# 02_Schematic.net
KiCad netlist of a schematic drawn in Altium Designer
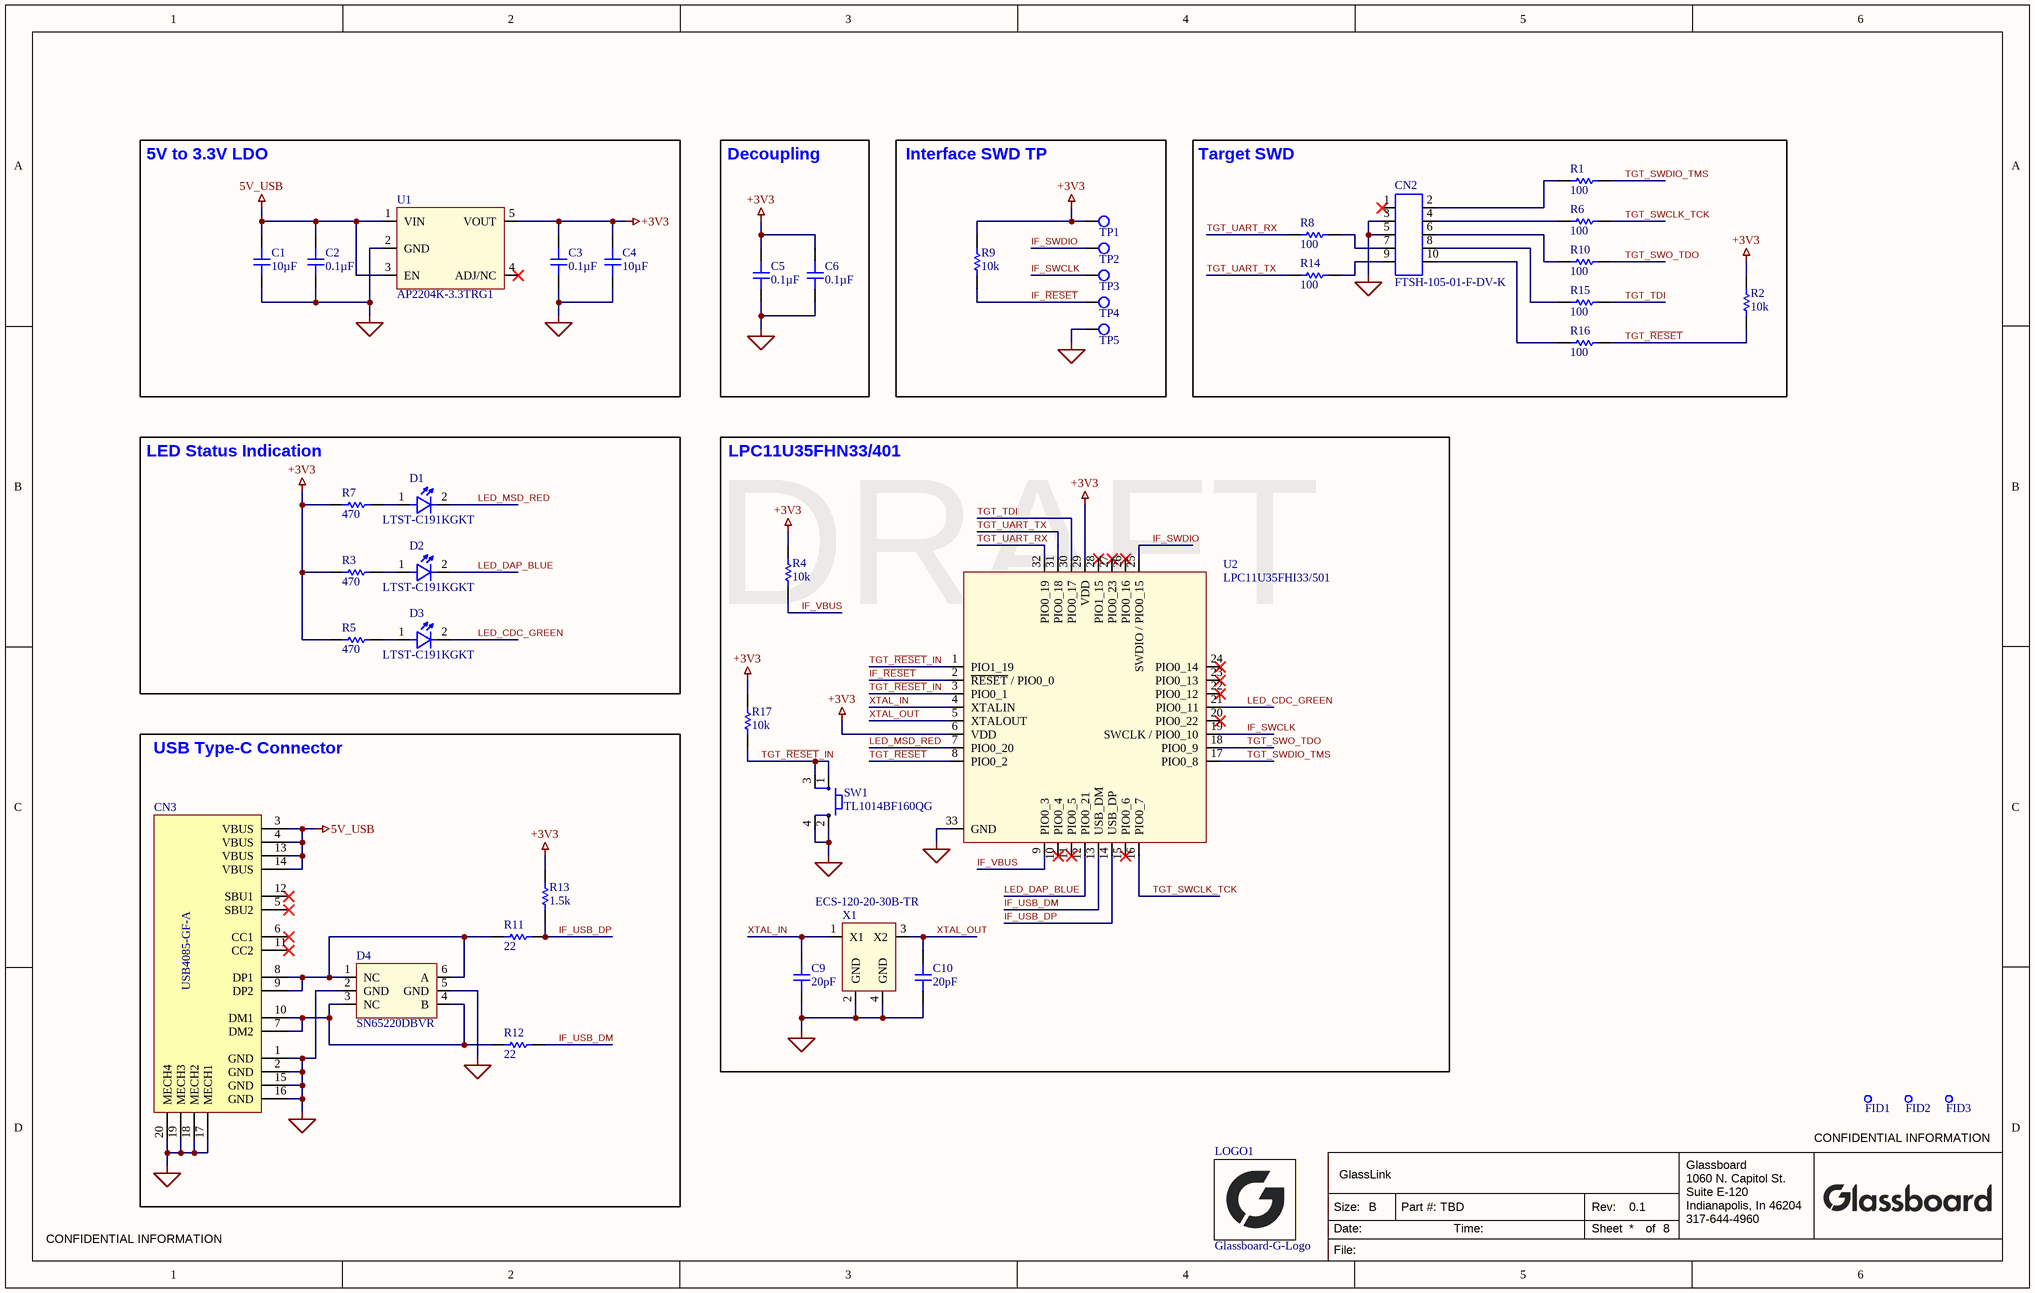
[diagram p0: [02] Schematic.SchDoc]

(export (version "E")
  (design (tool "Eeschema 10.0.6"))
  (components
    (comp (ref "C1")
      (value "10µF")
      (footprint "CAPC0402(1005)70_L")
      (description "CAP CER 10UF 6.3V X5R 0402")
      (fields
        (field (name "PART NUMBER") "CC0402MRX5R5BB106")
        (field (name "TOLERANCE") "0.2")
        (field (name "PUBLISHER") "Randy Parmerlee")
      )
      (libsource (lib "Glassboard Component Database") (part "Capacitor - Non Polarized"))
    )
    (comp (ref "C2")
      (value "0.1µF")
      (footprint "CAPC0402(1005)70_L")
      (description "CAP CER 0.1UF 10V X5R 0402")
      (fields
        (field (name "PART NUMBER") "CGA2B2X5R1A104M050BA")
        (field (name "TOLERANCE") "0.2")
        (field (name "PUBLISHER") "Drew Westrick")
      )
      (libsource (lib "Glassboard Component Database") (part "Capacitor - Non Polarized"))
    )
    (comp (ref "C3")
      (value "0.1µF")
      (footprint "CAPC0402(1005)70_L")
      (description "CAP CER 0.1UF 10V X5R 0402")
      (fields
        (field (name "PART NUMBER") "CGA2B2X5R1A104M050BA")
        (field (name "TOLERANCE") "0.2")
        (field (name "PUBLISHER") "Drew Westrick")
      )
      (libsource (lib "Glassboard Component Database") (part "Capacitor - Non Polarized"))
    )
    (comp (ref "C4")
      (value "10µF")
      (footprint "CAPC0402(1005)70_L")
      (description "CAP CER 10UF 6.3V X5R 0402")
      (fields
        (field (name "PART NUMBER") "CC0402MRX5R5BB106")
        (field (name "TOLERANCE") "0.2")
        (field (name "PUBLISHER") "Randy Parmerlee")
      )
      (libsource (lib "Glassboard Component Database") (part "Capacitor - Non Polarized"))
    )
    (comp (ref "C5")
      (value "0.1µF")
      (footprint "CAPC0402(1005)70_L")
      (description "CAP CER 0.1UF 10V X5R 0402")
      (fields
        (field (name "PART NUMBER") "CGA2B2X5R1A104M050BA")
        (field (name "TOLERANCE") "0.2")
        (field (name "PUBLISHER") "Drew Westrick")
      )
      (libsource (lib "Glassboard Component Database") (part "Capacitor - Non Polarized"))
    )
    (comp (ref "C6")
      (value "0.1µF")
      (footprint "CAPC0402(1005)70_L")
      (description "CAP CER 0.1UF 10V X5R 0402")
      (fields
        (field (name "PART NUMBER") "CGA2B2X5R1A104M050BA")
        (field (name "TOLERANCE") "0.2")
        (field (name "PUBLISHER") "Drew Westrick")
      )
      (libsource (lib "Glassboard Component Database") (part "Capacitor - Non Polarized"))
    )
    (comp (ref "C9")
      (value "20pF")
      (footprint "CAPC0402(1005)70_L")
      (description "CAP CER 20PF 50V C0G/NPO 0402")
      (fields
        (field (name "PART NUMBER") "CC0402JRNPO9BN200")
        (field (name "TOLERANCE") "0.05")
        (field (name "PUBLISHER") "Randy Parmerlee")
      )
      (libsource (lib "Glassboard Component Database") (part "Capacitor - Non Polarized"))
    )
    (comp (ref "C10")
      (value "20pF")
      (footprint "CAPC0402(1005)70_L")
      (description "CAP CER 20PF 50V C0G/NPO 0402")
      (fields
        (field (name "PART NUMBER") "CC0402JRNPO9BN200")
        (field (name "TOLERANCE") "0.05")
        (field (name "PUBLISHER") "Randy Parmerlee")
      )
      (libsource (lib "Glassboard Component Database") (part "Capacitor - Non Polarized"))
    )
    (comp (ref "CN2")
      (value "FTSH-105-01-F-DV-K")
      (footprint "FTSH-105-01-F-DV-K")
      (description "CONN HEADER 10POS DUAL .05\" SMD")
      (fields
        (field (name "MANUFACTURER") "Samtec Inc")
        (field (name "DISTRIBUTOR 1 PART NUMBER") "SAM8796-ND")
        (field (name "PUBLISHER") "Drew Westrick")
      )
      (libsource (lib "Glassboard Component Database") (part "CONN HEADER 10 POS DUAL ROW"))
    )
    (comp (ref "CN3")
      (value "USB4085-GF-A")
      (footprint "USB4085-GF-A")
      (description "CONN RCPT USB2.0 TYPEC 16POS")
      (fields
        (field (name "MANUFACTURER") "GCT")
        (field (name "DISTRIBUTOR 1 PART NUMBER") "2073-USB4085-GF-ACT-ND")
        (field (name "PUBLISHER") "Stephen Murphy")
      )
      (libsource (lib "Glassboard Component Database") (part "USB4085-GF-A"))
    )
    (comp (ref "D1")
      (value "LTST-C191KGKT")
      (footprint "LTST-C191KGKT")
      (description "LED GREEN CLEAR THIN 0603 SMD")
      (fields
        (field (name "MANUFACTURER") "Lite-On Inc")
        (field (name "DISTRIBUTOR 1 PART NUMBER") "160-1446-1-ND")
        (field (name "PUBLISHER") "Randy Parmerlee")
      )
      (libsource (lib "Glassboard Component Database") (part "Standard LED"))
    )
    (comp (ref "D2")
      (value "LTST-C191KGKT")
      (footprint "LTST-C191KGKT")
      (description "LED GREEN CLEAR THIN 0603 SMD")
      (fields
        (field (name "MANUFACTURER") "Lite-On Inc")
        (field (name "DISTRIBUTOR 1 PART NUMBER") "160-1446-1-ND")
        (field (name "PUBLISHER") "Randy Parmerlee")
      )
      (libsource (lib "Glassboard Component Database") (part "Standard LED"))
    )
    (comp (ref "D3")
      (value "LTST-C191KGKT")
      (footprint "LTST-C191KGKT")
      (description "LED GREEN CLEAR THIN 0603 SMD")
      (fields
        (field (name "MANUFACTURER") "Lite-On Inc")
        (field (name "DISTRIBUTOR 1 PART NUMBER") "160-1446-1-ND")
        (field (name "PUBLISHER") "Randy Parmerlee")
      )
      (libsource (lib "Glassboard Component Database") (part "Standard LED"))
    )
    (comp (ref "D4")
      (value "SN65220DBVR")
      (footprint "SN65220DBVR-L")
      (description "IC SINGLE USB PORT TVS SOT-23-6")
      (fields
        (field (name "VOLTAGE") "5V")
        (field (name "MANUFACTURER") "Texas Instruments")
        (field (name "PUBLISHER") "Randy Parmerlee")
      )
      (libsource (lib "Glassboard Component Database") (part "SN65220DBVR"))
    )
    (comp (ref "FID1")
      (value "FID")
      (footprint "fid_30mil")
      (description "Surface Mount Fiducials")
      (fields (field (name "PART NUMBER") "Fiducial") (field (name "PUBLISHER") "Randy Parmerlee"))
      (libsource (lib "Glassboard Component Database") (part "Fiducial"))
    )
    (comp (ref "FID2")
      (value "FID")
      (footprint "fid_30mil")
      (description "Surface Mount Fiducials")
      (fields (field (name "PART NUMBER") "Fiducial") (field (name "PUBLISHER") "Randy Parmerlee"))
      (libsource (lib "Glassboard Component Database") (part "Fiducial"))
    )
    (comp (ref "FID3")
      (value "FID")
      (footprint "fid_30mil")
      (description "Surface Mount Fiducials")
      (fields (field (name "PART NUMBER") "Fiducial") (field (name "PUBLISHER") "Randy Parmerlee"))
      (libsource (lib "Glassboard Component Database") (part "Fiducial"))
    )
    (comp (ref "LOGO1")
      (value "Glassboard-G-Logo")
      (footprint "GLASSBOARD-G-5X5MM")
      (description "Glassboard Company Logo 5x5mm")
      (fields
        (field (name "PART NUMBER") "Glassboard-G-Logo-5x5MM")
        (field (name "PUBLISHER") "Stephen Murphy")
      )
      (libsource (lib "Glassboard Component Database") (part "Glassboard-G-Logo"))
    )
    (comp (ref "R1")
      (value "100")
      (footprint "RESC0402(1005)_L")
      (description "RES SMD 100 OHM 1% 1/16W 0402")
      (fields
        (field (name "PART NUMBER") "RC0402FR-07100RL")
        (field (name "TOLERANCE") "0.01")
        (field (name "PUBLISHER") "Randy Parmerlee")
      )
      (libsource (lib "Glassboard Component Database") (part "Resistor - Standard"))
    )
    (comp (ref "R2")
      (value "10k")
      (footprint "RESC0402(1005)_L")
      (description "RES SMD 10K OHM 1% 1/16W 0402")
      (fields
        (field (name "PART NUMBER") "RC0402FR-0710KL")
        (field (name "TOLERANCE") "0.01")
        (field (name "PUBLISHER") "Randy Parmerlee")
      )
      (libsource (lib "Glassboard Component Database") (part "Resistor - Standard"))
    )
    (comp (ref "R3")
      (value "470")
      (footprint "RESC0402(1005)_L")
      (description "RES SMD 470 OHM 1% 1/10W 0402")
      (fields
        (field (name "PART NUMBER") "ERJ-2RKF4700X")
        (field (name "TOLERANCE") "0.01")
        (field (name "PUBLISHER") "Drew Westrick")
      )
      (libsource (lib "Glassboard Component Database") (part "Resistor - Standard"))
    )
    (comp (ref "R4")
      (value "10k")
      (footprint "RESC0402(1005)_L")
      (description "RES SMD 10K OHM 1% 1/16W 0402")
      (fields
        (field (name "PART NUMBER") "RC0402FR-0710KL")
        (field (name "TOLERANCE") "0.01")
        (field (name "PUBLISHER") "Randy Parmerlee")
      )
      (libsource (lib "Glassboard Component Database") (part "Resistor - Standard"))
    )
    (comp (ref "R5")
      (value "470")
      (footprint "RESC0402(1005)_L")
      (description "RES SMD 470 OHM 1% 1/10W 0402")
      (fields
        (field (name "PART NUMBER") "ERJ-2RKF4700X")
        (field (name "TOLERANCE") "0.01")
        (field (name "PUBLISHER") "Drew Westrick")
      )
      (libsource (lib "Glassboard Component Database") (part "Resistor - Standard"))
    )
    (comp (ref "R6")
      (value "100")
      (footprint "RESC0402(1005)_L")
      (description "RES SMD 100 OHM 1% 1/16W 0402")
      (fields
        (field (name "PART NUMBER") "RC0402FR-07100RL")
        (field (name "TOLERANCE") "0.01")
        (field (name "PUBLISHER") "Randy Parmerlee")
      )
      (libsource (lib "Glassboard Component Database") (part "Resistor - Standard"))
    )
    (comp (ref "R7")
      (value "470")
      (footprint "RESC0402(1005)_L")
      (description "RES SMD 470 OHM 1% 1/10W 0402")
      (fields
        (field (name "PART NUMBER") "ERJ-2RKF4700X")
        (field (name "TOLERANCE") "0.01")
        (field (name "PUBLISHER") "Drew Westrick")
      )
      (libsource (lib "Glassboard Component Database") (part "Resistor - Standard"))
    )
    (comp (ref "R8")
      (value "100")
      (footprint "RESC0402(1005)_L")
      (description "RES SMD 100 OHM 1% 1/16W 0402")
      (fields
        (field (name "PART NUMBER") "RC0402FR-07100RL")
        (field (name "TOLERANCE") "0.01")
        (field (name "PUBLISHER") "Randy Parmerlee")
      )
      (libsource (lib "Glassboard Component Database") (part "Resistor - Standard"))
    )
    (comp (ref "R9")
      (value "10k")
      (footprint "RESC0402(1005)_L")
      (description "RES SMD 10K OHM 1% 1/16W 0402")
      (fields
        (field (name "PART NUMBER") "RC0402FR-0710KL")
        (field (name "TOLERANCE") "0.01")
        (field (name "PUBLISHER") "Randy Parmerlee")
      )
      (libsource (lib "Glassboard Component Database") (part "Resistor - Standard"))
    )
    (comp (ref "R10")
      (value "100")
      (footprint "RESC0402(1005)_L")
      (description "RES SMD 100 OHM 1% 1/16W 0402")
      (fields
        (field (name "PART NUMBER") "RC0402FR-07100RL")
        (field (name "TOLERANCE") "0.01")
        (field (name "PUBLISHER") "Randy Parmerlee")
      )
      (libsource (lib "Glassboard Component Database") (part "Resistor - Standard"))
    )
    (comp (ref "R11")
      (value "22")
      (footprint "RESC0402(1005)_L")
      (description "RES SMD 22 OHM 1% 1/16W 0402")
      (fields
        (field (name "PART NUMBER") "RC0402FR-0722RL")
        (field (name "TOLERANCE") "0.01")
        (field (name "PUBLISHER") "Randy Parmerlee")
      )
      (libsource (lib "Glassboard Component Database") (part "Resistor - Standard"))
    )
    (comp (ref "R12")
      (value "22")
      (footprint "RESC0402(1005)_L")
      (description "RES SMD 22 OHM 1% 1/16W 0402")
      (fields
        (field (name "PART NUMBER") "RC0402FR-0722RL")
        (field (name "TOLERANCE") "0.01")
        (field (name "PUBLISHER") "Randy Parmerlee")
      )
      (libsource (lib "Glassboard Component Database") (part "Resistor - Standard"))
    )
    (comp (ref "R13")
      (value "1.5k")
      (footprint "RESC0402(1005)_L")
      (description "RES SMD 1.5K OHM 1% 1/10W 0402")
      (fields
        (field (name "PART NUMBER") "ERJ-2RKF1501X")
        (field (name "TOLERANCE") "0.01")
        (field (name "PUBLISHER") "Drew Westrick")
      )
      (libsource (lib "Glassboard Component Database") (part "Resistor - Standard"))
    )
    (comp (ref "R14")
      (value "100")
      (footprint "RESC0402(1005)_L")
      (description "RES SMD 100 OHM 1% 1/16W 0402")
      (fields
        (field (name "PART NUMBER") "RC0402FR-07100RL")
        (field (name "TOLERANCE") "0.01")
        (field (name "PUBLISHER") "Randy Parmerlee")
      )
      (libsource (lib "Glassboard Component Database") (part "Resistor - Standard"))
    )
    (comp (ref "R15")
      (value "100")
      (footprint "RESC0402(1005)_L")
      (description "RES SMD 100 OHM 1% 1/16W 0402")
      (fields
        (field (name "PART NUMBER") "RC0402FR-07100RL")
        (field (name "TOLERANCE") "0.01")
        (field (name "PUBLISHER") "Randy Parmerlee")
      )
      (libsource (lib "Glassboard Component Database") (part "Resistor - Standard"))
    )
    (comp (ref "R16")
      (value "100")
      (footprint "RESC0402(1005)_L")
      (description "RES SMD 100 OHM 1% 1/16W 0402")
      (fields
        (field (name "PART NUMBER") "RC0402FR-07100RL")
        (field (name "TOLERANCE") "0.01")
        (field (name "PUBLISHER") "Randy Parmerlee")
      )
      (libsource (lib "Glassboard Component Database") (part "Resistor - Standard"))
    )
    (comp (ref "R17")
      (value "10k")
      (footprint "RESC0402(1005)_L")
      (description "RES SMD 10K OHM 1% 1/16W 0402")
      (fields
        (field (name "PART NUMBER") "RC0402FR-0710KL")
        (field (name "TOLERANCE") "0.01")
        (field (name "PUBLISHER") "Randy Parmerlee")
      )
      (libsource (lib "Glassboard Component Database") (part "Resistor - Standard"))
    )
    (comp (ref "SW1")
      (value "TL1014BF160QG")
      (footprint "TL1014BF160QG")
      (description "SWITCH TACTILE SPST-NO 0.05A 12V")
      (fields
        (field (name "MANUFACTURER") "E-Switch")
        (field (name "DISTRIBUTOR 1 PART NUMBER") "EG5042CT-ND")
        (field (name "PUBLISHER") "Randy Parmerlee")
      )
      (libsource (lib "Glassboard Component Database") (part "TL1014BF160QG"))
    )
    (comp (ref "TP1")
      (value "TESTFIXTURE_16MM")
      (footprint "TESTFIXTURE_16MM")
      (description "TEST POINT ROUND 1.6mm")
      (fields (field (name "MANUFACTURER") "GlassBoard") (field (name "PUBLISHER") "Ethan Harmon"))
      (libsource (lib "Glassboard Component Database") (part "SINGLE_TP"))
    )
    (comp (ref "TP2")
      (value "TESTFIXTURE_16MM")
      (footprint "TESTFIXTURE_16MM")
      (description "TEST POINT ROUND 1.6mm")
      (fields (field (name "MANUFACTURER") "GlassBoard") (field (name "PUBLISHER") "Ethan Harmon"))
      (libsource (lib "Glassboard Component Database") (part "SINGLE_TP"))
    )
    (comp (ref "TP3")
      (value "TESTFIXTURE_16MM")
      (footprint "TESTFIXTURE_16MM")
      (description "TEST POINT ROUND 1.6mm")
      (fields (field (name "MANUFACTURER") "GlassBoard") (field (name "PUBLISHER") "Ethan Harmon"))
      (libsource (lib "Glassboard Component Database") (part "SINGLE_TP"))
    )
    (comp (ref "TP4")
      (value "TESTFIXTURE_16MM")
      (footprint "TESTFIXTURE_16MM")
      (description "TEST POINT ROUND 1.6mm")
      (fields (field (name "MANUFACTURER") "GlassBoard") (field (name "PUBLISHER") "Ethan Harmon"))
      (libsource (lib "Glassboard Component Database") (part "SINGLE_TP"))
    )
    (comp (ref "TP5")
      (value "TESTFIXTURE_16MM")
      (footprint "TESTFIXTURE_16MM")
      (description "TEST POINT ROUND 1.6mm")
      (fields (field (name "MANUFACTURER") "GlassBoard") (field (name "PUBLISHER") "Ethan Harmon"))
      (libsource (lib "Glassboard Component Database") (part "SINGLE_TP"))
    )
    (comp (ref "U1")
      (value "AP2204K-3.3TRG1")
      (footprint "AP2204K-3.3TRG1_L")
      (description "IC REG LDO 3.3V 0.15A SOT25")
      (fields
        (field (name "VOLTAGE") "24V")
        (field (name "MANUFACTURER") "Diodes Incorporated")
        (field (name "PUBLISHER") "Randy Parmerlee")
      )
      (libsource (lib "Glassboard Component Database") (part "AP2204K-3.3TRG1"))
    )
    (comp (ref "U2")
      (value "LPC11U35FHI33/501")
      (footprint "LPC11U35FHI33/501")
      (description "IC MCU 32BIT 64KB FLASH 32HVQFN")
      (fields
        (field (name "VOLTAGE") "3.3V")
        (field (name "MANUFACTURER") "NXP USA Inc.")
        (field (name "PUBLISHER") "Stephen Murphy")
      )
      (libsource (lib "Glassboard Component Database") (part "LPC11U35FHN33/401"))
    )
    (comp (ref "X1")
      (value "ECS-120-20-30B-TR")
      (footprint "DFN370P500X85-4N")
      (description "Crystal 12.0000MHz 30ppm 20pF 80 Ohm -20°C - 70°C Surface Mount 4-SMD, No Lead (DFN, LCC)")
      (fields
        (field (name "MANUFACTURER") "ECS Inc.")
        (field (name "DISTRIBUTOR 1 PART NUMBER") "XC1118CT-ND")
        (field (name "PUBLISHER") "Randy Parmerlee")
      )
      (libsource (lib "Glassboard Component Database") (part "ECS-120-20-30B-TR"))
    )
  )
  (nets
    (net (code "1") (name "+3V3") (class "Default")
      (node (ref "C3") (pin "2") (pinfunction "2_2") (pintype "passive"))
      (node (ref "C4") (pin "2") (pinfunction "2_2") (pintype "passive"))
      (node (ref "C5") (pin "2") (pinfunction "2_2") (pintype "passive"))
      (node (ref "C6") (pin "2") (pinfunction "2_2") (pintype "passive"))
      (node (ref "R13") (pin "2") (pinfunction "2_2") (pintype "passive"))
      (node (ref "R17") (pin "2") (pinfunction "2_2") (pintype "passive"))
      (node (ref "R2") (pin "2") (pinfunction "2_2") (pintype "passive"))
      (node (ref "R3") (pin "1") (pinfunction "1_1") (pintype "passive"))
      (node (ref "R4") (pin "2") (pinfunction "2_2") (pintype "passive"))
      (node (ref "R5") (pin "1") (pinfunction "1_1") (pintype "passive"))
      (node (ref "R7") (pin "1") (pinfunction "1_1") (pintype "passive"))
      (node (ref "R9") (pin "2") (pinfunction "2_2") (pintype "passive"))
      (node (ref "TP1") (pin "1") (pintype "passive"))
      (node (ref "U1") (pin "5") (pinfunction "VOUT_5") (pintype "passive"))
      (node (ref "U2") (pin "29") (pinfunction "VDD_29") (pintype "passive"))
      (node (ref "U2") (pin "6") (pinfunction "VDD_6") (pintype "passive"))
    )
    (net (code "2") (name "/IF_SWCLK") (class "Default")
      (node (ref "TP3") (pin "1") (pintype "passive"))
      (node (ref "U2") (pin "19") (pinfunction "SWCLK_/_PIO0_10_19") (pintype "passive"))
    )
    (net (code "3") (name "/IF_SWDIO") (class "Default")
      (node (ref "TP2") (pin "1") (pintype "passive"))
      (node (ref "U2") (pin "25") (pinfunction "SWDIO_/_PIO0_15_25") (pintype "passive"))
    )
    (net (code "4") (name "/IF_USB_DM") (class "Default")
      (node (ref "R12") (pin "2") (pinfunction "2_2") (pintype "passive"))
      (node (ref "U2") (pin "13") (pinfunction "USB_DM_13") (pintype "passive"))
    )
    (net (code "5") (name "/IF_USB_DP") (class "Default")
      (node (ref "R11") (pin "2") (pinfunction "2_2") (pintype "passive"))
      (node (ref "R13") (pin "1") (pinfunction "1_1") (pintype "passive"))
      (node (ref "U2") (pin "14") (pinfunction "USB_DP_14") (pintype "passive"))
    )
    (net (code "6") (name "/IF_VBUS") (class "Default")
      (node (ref "R4") (pin "1") (pinfunction "1_1") (pintype "passive"))
      (node (ref "U2") (pin "9") (pinfunction "PIO0_3_9") (pintype "passive"))
    )
    (net (code "7") (name "/IF_~{RESET}") (class "Default")
      (node (ref "R9") (pin "1") (pinfunction "1_1") (pintype "passive"))
      (node (ref "TP4") (pin "1") (pintype "passive"))
      (node (ref "U2") (pin "2") (pinfunction "~{RESET}_/_PIO0_0_2") (pintype "passive"))
    )
    (net (code "8") (name "/LED_CDC_GREEN") (class "Default")
      (node (ref "D3") (pin "2") (pinfunction "2_2") (pintype "passive"))
      (node (ref "U2") (pin "21") (pinfunction "PIO0_11_21") (pintype "passive"))
    )
    (net (code "9") (name "/LED_DAP_BLUE") (class "Default")
      (node (ref "D2") (pin "2") (pinfunction "2_2") (pintype "passive"))
      (node (ref "U2") (pin "12") (pinfunction "PIO0_21_12") (pintype "passive"))
    )
    (net (code "10") (name "/LED_MSD_RED") (class "Default")
      (node (ref "D1") (pin "2") (pinfunction "2_2") (pintype "passive"))
      (node (ref "U2") (pin "7") (pinfunction "PIO0_20_7") (pintype "passive"))
    )
    (net (code "11") (name "/TGT_SWCLK_TCK") (class "Default")
      (node (ref "R6") (pin "2") (pinfunction "2_2") (pintype "passive"))
      (node (ref "U2") (pin "16") (pinfunction "PIO0_7_16") (pintype "passive"))
    )
    (net (code "12") (name "/TGT_SWDIO_TMS") (class "Default")
      (node (ref "R1") (pin "2") (pinfunction "2_2") (pintype "passive"))
      (node (ref "U2") (pin "17") (pinfunction "PIO0_8_17") (pintype "passive"))
    )
    (net (code "13") (name "/TGT_SWO_TDO") (class "Default")
      (node (ref "R10") (pin "2") (pinfunction "2_2") (pintype "passive"))
      (node (ref "U2") (pin "18") (pinfunction "PIO0_9_18") (pintype "passive"))
    )
    (net (code "14") (name "/TGT_TDI") (class "Default")
      (node (ref "R15") (pin "2") (pinfunction "2_2") (pintype "passive"))
      (node (ref "U2") (pin "30") (pinfunction "PIO0_17_30") (pintype "passive"))
    )
    (net (code "15") (name "/TGT_UART_RX") (class "Default")
      (node (ref "R8") (pin "1") (pinfunction "1_1") (pintype "passive"))
      (node (ref "U2") (pin "32") (pinfunction "PIO0_19_32") (pintype "passive"))
    )
    (net (code "16") (name "/TGT_UART_TX") (class "Default")
      (node (ref "R14") (pin "1") (pinfunction "1_1") (pintype "passive"))
      (node (ref "U2") (pin "31") (pinfunction "PIO0_18_31") (pintype "passive"))
    )
    (net (code "17") (name "/TGT_~{RESET}") (class "Default")
      (node (ref "R16") (pin "2") (pinfunction "2_2") (pintype "passive"))
      (node (ref "R2") (pin "1") (pinfunction "1_1") (pintype "passive"))
      (node (ref "U2") (pin "8") (pinfunction "PIO0_2_8") (pintype "passive"))
    )
    (net (code "18") (name "/TGT_~{RESET}_IN") (class "Default")
      (node (ref "R17") (pin "1") (pinfunction "1_1") (pintype "passive"))
      (node (ref "SW1") (pin "1") (pinfunction "1_1") (pintype "passive"))
      (node (ref "SW1") (pin "3") (pinfunction "3_3") (pintype "passive"))
      (node (ref "U2") (pin "1") (pinfunction "PIO1_19_1") (pintype "passive"))
      (node (ref "U2") (pin "3") (pinfunction "PIO0_1_3") (pintype "passive"))
    )
    (net (code "19") (name "/XTAL_IN") (class "Default")
      (node (ref "C9") (pin "1") (pinfunction "1_1") (pintype "passive"))
      (node (ref "U2") (pin "4") (pinfunction "XTALIN_4") (pintype "passive"))
      (node (ref "X1") (pin "1") (pinfunction "X1_1") (pintype "passive"))
    )
    (net (code "20") (name "/XTAL_OUT") (class "Default")
      (node (ref "C10") (pin "1") (pinfunction "1_1") (pintype "passive"))
      (node (ref "U2") (pin "5") (pinfunction "XTALOUT_5") (pintype "passive"))
      (node (ref "X1") (pin "3") (pinfunction "X2_3") (pintype "passive"))
    )
    (net (code "21") (name "5V_USB") (class "Default")
      (node (ref "C1") (pin "2") (pinfunction "2_2") (pintype "passive"))
      (node (ref "C2") (pin "2") (pinfunction "2_2") (pintype "passive"))
      (node (ref "CN3") (pin "13") (pinfunction "VBUS_13") (pintype "passive"))
      (node (ref "CN3") (pin "14") (pinfunction "VBUS_14") (pintype "passive"))
      (node (ref "CN3") (pin "3") (pinfunction "VBUS_3") (pintype "passive"))
      (node (ref "CN3") (pin "4") (pinfunction "VBUS_4") (pintype "passive"))
      (node (ref "U1") (pin "1") (pinfunction "VIN_1") (pintype "passive"))
      (node (ref "U1") (pin "3") (pinfunction "EN_3") (pintype "passive"))
    )
    (net (code "22") (name "GND") (class "Default")
      (node (ref "C1") (pin "1") (pinfunction "1_1") (pintype "passive"))
      (node (ref "C10") (pin "2") (pinfunction "2_2") (pintype "passive"))
      (node (ref "C2") (pin "1") (pinfunction "1_1") (pintype "passive"))
      (node (ref "C3") (pin "1") (pinfunction "1_1") (pintype "passive"))
      (node (ref "C4") (pin "1") (pinfunction "1_1") (pintype "passive"))
      (node (ref "C5") (pin "1") (pinfunction "1_1") (pintype "passive"))
      (node (ref "C6") (pin "1") (pinfunction "1_1") (pintype "passive"))
      (node (ref "C9") (pin "2") (pinfunction "2_2") (pintype "passive"))
      (node (ref "CN2") (pin "3") (pinfunction "3_3") (pintype "passive"))
      (node (ref "CN2") (pin "5") (pinfunction "5_5") (pintype "passive"))
      (node (ref "CN3") (pin "1") (pinfunction "GND_1") (pintype "passive"))
      (node (ref "CN3") (pin "15") (pinfunction "GND_15") (pintype "passive"))
      (node (ref "CN3") (pin "16") (pinfunction "GND_16") (pintype "passive"))
      (node (ref "CN3") (pin "17") (pinfunction "MECH1_17") (pintype "passive"))
      (node (ref "CN3") (pin "18") (pinfunction "MECH2_18") (pintype "passive"))
      (node (ref "CN3") (pin "19") (pinfunction "MECH3_19") (pintype "passive"))
      (node (ref "CN3") (pin "2") (pinfunction "GND_2") (pintype "passive"))
      (node (ref "CN3") (pin "20") (pinfunction "MECH4_20") (pintype "passive"))
      (node (ref "D4") (pin "2") (pinfunction "GND_2") (pintype "passive"))
      (node (ref "D4") (pin "5") (pinfunction "GND_5") (pintype "passive"))
      (node (ref "SW1") (pin "2") (pinfunction "2_2") (pintype "passive"))
      (node (ref "SW1") (pin "4") (pinfunction "4_4") (pintype "passive"))
      (node (ref "TP5") (pin "1") (pintype "passive"))
      (node (ref "U1") (pin "2") (pinfunction "GND_2") (pintype "passive"))
      (node (ref "U2") (pin "33") (pinfunction "GND_33") (pintype "passive"))
      (node (ref "X1") (pin "2") (pinfunction "GND_2") (pintype "passive"))
      (node (ref "X1") (pin "4") (pinfunction "GND_4") (pintype "passive"))
    )
    (net (code "23") (name "Net-(CN2-Pad2)") (class "Default")
      (node (ref "CN2") (pin "2") (pinfunction "2_2") (pintype "passive"))
      (node (ref "R1") (pin "1") (pinfunction "1_1") (pintype "passive"))
    )
    (net (code "24") (name "Net-(CN2-Pad4)") (class "Default")
      (node (ref "CN2") (pin "4") (pinfunction "4_4") (pintype "passive"))
      (node (ref "R6") (pin "1") (pinfunction "1_1") (pintype "passive"))
    )
    (net (code "25") (name "Net-(CN2-Pad6)") (class "Default")
      (node (ref "CN2") (pin "6") (pinfunction "6_6") (pintype "passive"))
      (node (ref "R10") (pin "1") (pinfunction "1_1") (pintype "passive"))
    )
    (net (code "26") (name "Net-(CN2-Pad7)") (class "Default")
      (node (ref "CN2") (pin "7") (pinfunction "7_7") (pintype "passive"))
      (node (ref "R8") (pin "2") (pinfunction "2_2") (pintype "passive"))
    )
    (net (code "27") (name "Net-(CN2-Pad8)") (class "Default")
      (node (ref "CN2") (pin "8") (pinfunction "8_8") (pintype "passive"))
      (node (ref "R15") (pin "1") (pinfunction "1_1") (pintype "passive"))
    )
    (net (code "28") (name "Net-(CN2-Pad9)") (class "Default")
      (node (ref "CN2") (pin "9") (pinfunction "9_9") (pintype "passive"))
      (node (ref "R14") (pin "2") (pinfunction "2_2") (pintype "passive"))
    )
    (net (code "29") (name "Net-(CN2-Pad10)") (class "Default")
      (node (ref "CN2") (pin "10") (pinfunction "10_10") (pintype "passive"))
      (node (ref "R16") (pin "1") (pinfunction "1_1") (pintype "passive"))
    )
    (net (code "30") (name "Net-(CN3-DM1)") (class "Default")
      (node (ref "CN3") (pin "10") (pinfunction "DM1_10") (pintype "passive"))
      (node (ref "CN3") (pin "7") (pinfunction "DM2_7") (pintype "passive"))
      (node (ref "D4") (pin "3") (pinfunction "NC_3") (pintype "passive"))
      (node (ref "D4") (pin "4") (pinfunction "B_4") (pintype "passive"))
      (node (ref "R12") (pin "1") (pinfunction "1_1") (pintype "passive"))
    )
    (net (code "31") (name "Net-(CN3-DP1)") (class "Default")
      (node (ref "CN3") (pin "8") (pinfunction "DP1_8") (pintype "passive"))
      (node (ref "CN3") (pin "9") (pinfunction "DP2_9") (pintype "passive"))
      (node (ref "D4") (pin "1") (pinfunction "NC_1") (pintype "passive"))
      (node (ref "D4") (pin "6") (pinfunction "A_6") (pintype "passive"))
      (node (ref "R11") (pin "1") (pinfunction "1_1") (pintype "passive"))
    )
    (net (code "32") (name "Net-(D1-Pad1)") (class "Default")
      (node (ref "D1") (pin "1") (pinfunction "1_1") (pintype "passive"))
      (node (ref "R7") (pin "2") (pinfunction "2_2") (pintype "passive"))
    )
    (net (code "33") (name "Net-(D2-Pad1)") (class "Default")
      (node (ref "D2") (pin "1") (pinfunction "1_1") (pintype "passive"))
      (node (ref "R3") (pin "2") (pinfunction "2_2") (pintype "passive"))
    )
    (net (code "34") (name "Net-(D3-Pad1)") (class "Default")
      (node (ref "D3") (pin "1") (pinfunction "1_1") (pintype "passive"))
      (node (ref "R5") (pin "2") (pinfunction "2_2") (pintype "passive"))
    )
    (net (code "35") (name "unconnected-(CN2-Pad1)") (class "Default")
      (node (ref "CN2") (pin "1") (pinfunction "1_1") (pintype "passive+no_connect"))
    )
    (net (code "36") (name "unconnected-(CN3-CC1-Pad6)") (class "Default")
      (node (ref "CN3") (pin "6") (pinfunction "CC1_6") (pintype "passive+no_connect"))
    )
    (net (code "37") (name "unconnected-(CN3-CC2-Pad11)") (class "Default")
      (node (ref "CN3") (pin "11") (pinfunction "CC2_11") (pintype "passive+no_connect"))
    )
    (net (code "38") (name "unconnected-(CN3-SBU1-Pad12)") (class "Default")
      (node (ref "CN3") (pin "12") (pinfunction "SBU1_12") (pintype "passive+no_connect"))
    )
    (net (code "39") (name "unconnected-(CN3-SBU2-Pad5)") (class "Default")
      (node (ref "CN3") (pin "5") (pinfunction "SBU2_5") (pintype "passive+no_connect"))
    )
    (net (code "40") (name "unconnected-(FID1-Pad0)") (class "Default")
      (node (ref "FID1") (pin "0") (pinfunction "0_0") (pintype "passive"))
    )
    (net (code "41") (name "unconnected-(FID2-Pad0)") (class "Default")
      (node (ref "FID2") (pin "0") (pinfunction "0_0") (pintype "passive"))
    )
    (net (code "42") (name "unconnected-(FID3-Pad0)") (class "Default")
      (node (ref "FID3") (pin "0") (pinfunction "0_0") (pintype "passive"))
    )
    (net (code "43") (name "unconnected-(U1-ADJ{slash}NC-Pad4)") (class "Default")
      (node (ref "U1") (pin "4") (pinfunction "ADJ/NC_4") (pintype "passive+no_connect"))
    )
    (net (code "44") (name "unconnected-(U2-PIO0_4-Pad10)") (class "Default")
      (node (ref "U2") (pin "10") (pinfunction "PIO0_4_10") (pintype "passive+no_connect"))
    )
    (net (code "45") (name "unconnected-(U2-PIO0_5-Pad11)") (class "Default")
      (node (ref "U2") (pin "11") (pinfunction "PIO0_5_11") (pintype "passive+no_connect"))
    )
    (net (code "46") (name "unconnected-(U2-PIO0_6-Pad15)") (class "Default")
      (node (ref "U2") (pin "15") (pinfunction "PIO0_6_15") (pintype "passive+no_connect"))
    )
    (net (code "47") (name "unconnected-(U2-PIO0_12-Pad22)") (class "Default")
      (node (ref "U2") (pin "22") (pinfunction "PIO0_12_22") (pintype "passive+no_connect"))
    )
    (net (code "48") (name "unconnected-(U2-PIO0_13-Pad23)") (class "Default")
      (node (ref "U2") (pin "23") (pinfunction "PIO0_13_23") (pintype "passive+no_connect"))
    )
    (net (code "49") (name "unconnected-(U2-PIO0_14-Pad24)") (class "Default")
      (node (ref "U2") (pin "24") (pinfunction "PIO0_14_24") (pintype "passive+no_connect"))
    )
    (net (code "50") (name "unconnected-(U2-PIO0_16-Pad26)") (class "Default")
      (node (ref "U2") (pin "26") (pinfunction "PIO0_16_26") (pintype "passive+no_connect"))
    )
    (net (code "51") (name "unconnected-(U2-PIO0_22-Pad20)") (class "Default")
      (node (ref "U2") (pin "20") (pinfunction "PIO0_22_20") (pintype "passive+no_connect"))
    )
    (net (code "52") (name "unconnected-(U2-PIO0_23-Pad27)") (class "Default")
      (node (ref "U2") (pin "27") (pinfunction "PIO0_23_27") (pintype "passive+no_connect"))
    )
    (net (code "53") (name "unconnected-(U2-PIO1_15-Pad28)") (class "Default")
      (node (ref "U2") (pin "28") (pinfunction "PIO1_15_28") (pintype "passive+no_connect"))
    )
  )
)
